# neuztech-4.net
KiCad netlist of a schematic drawn in EAGLE
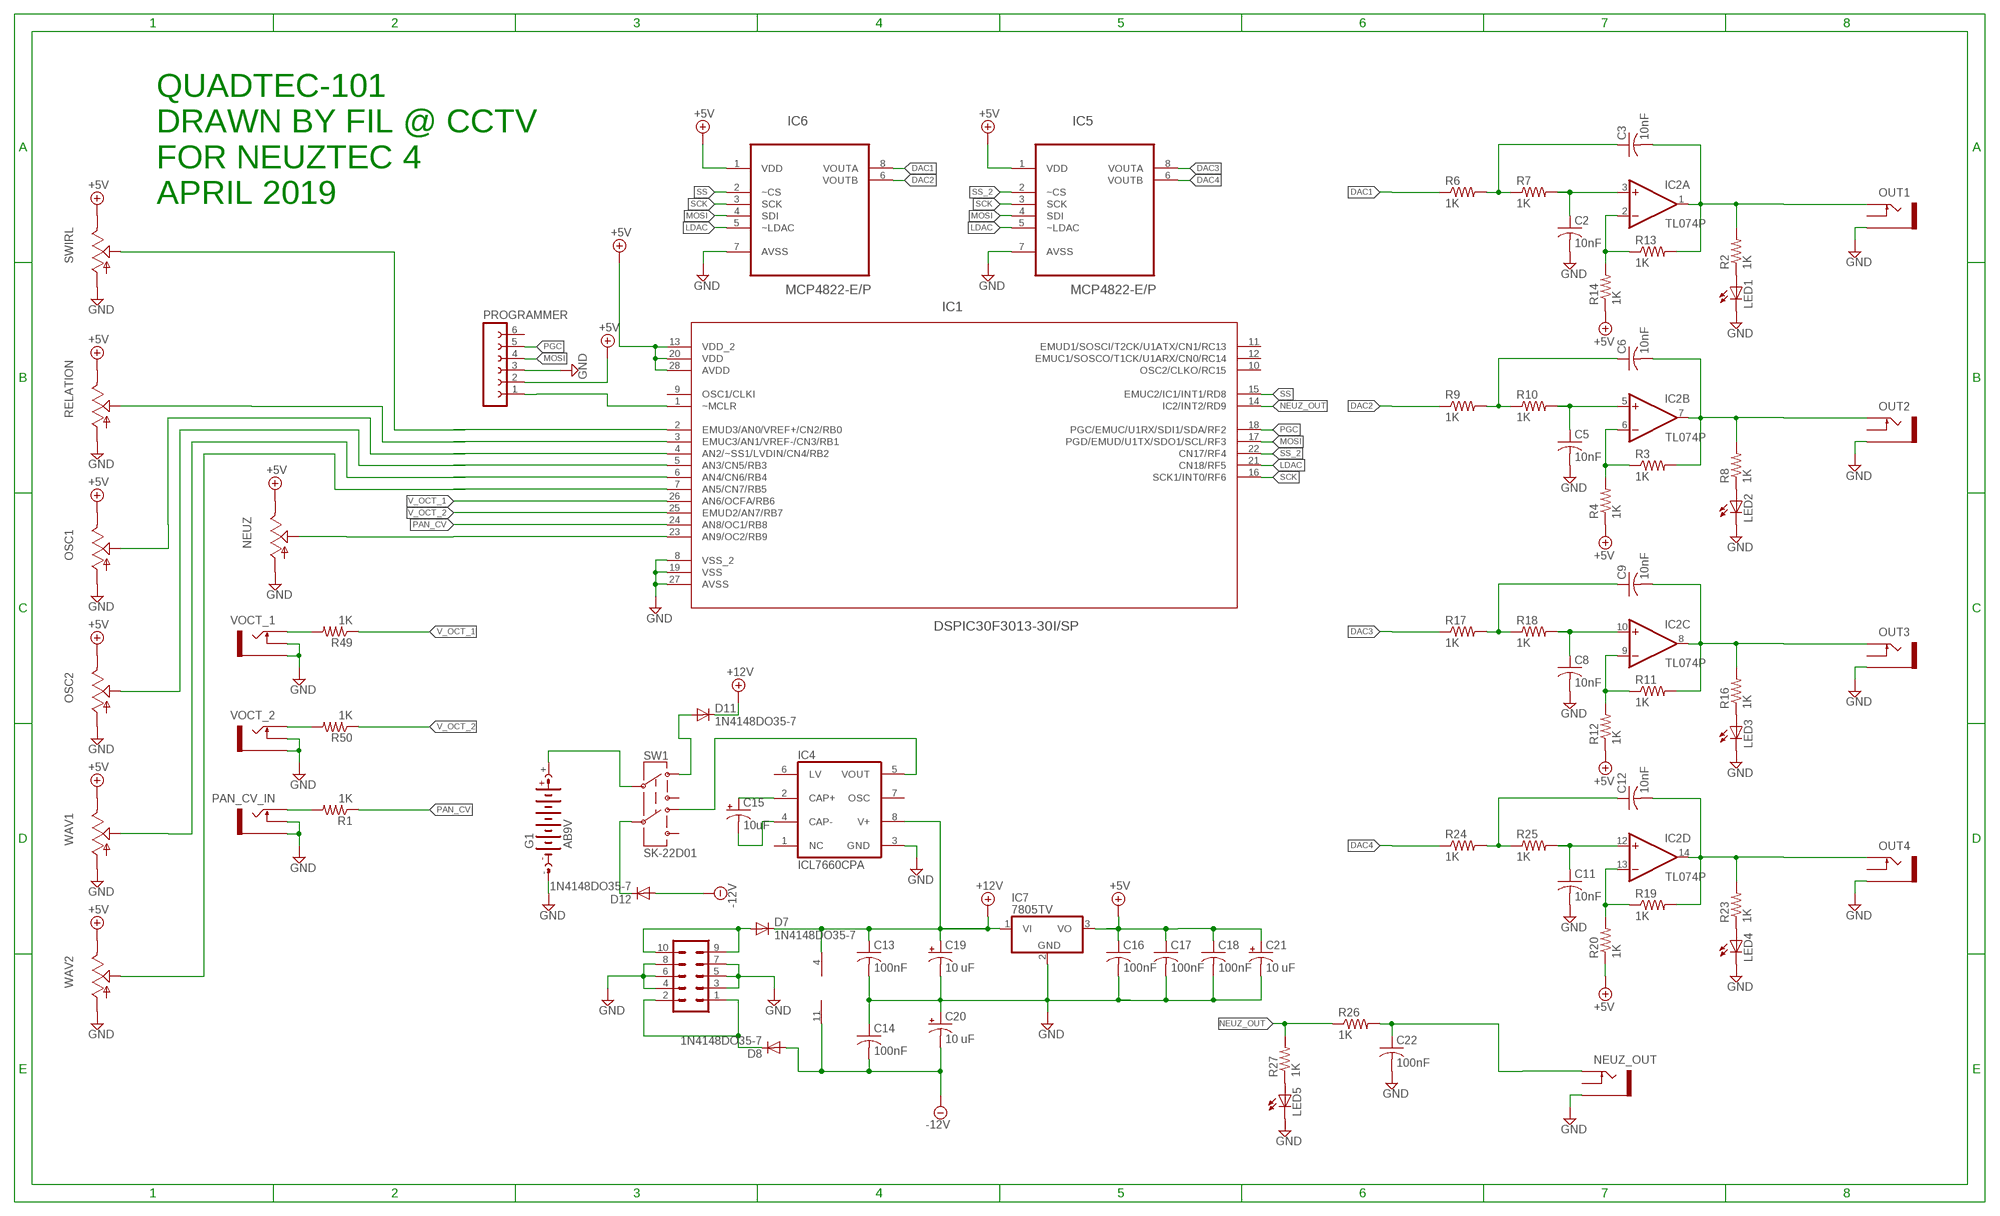
[diagram p0: schematic, sheet 1]

(export (version "E")
  (design (tool "Eeschema 10.0.6"))
  (components
    (comp (ref "C2")
      (value "10nF")
      (footprint "eagle-import:C050-035X075")
      (libsource (lib "eagle-import") (part "C-US050-035X075"))
    )
    (comp (ref "C3")
      (value "10nF")
      (footprint "eagle-import:C050-035X075")
      (libsource (lib "eagle-import") (part "C-US050-035X075"))
    )
    (comp (ref "C5")
      (value "10nF")
      (footprint "eagle-import:C050-035X075")
      (libsource (lib "eagle-import") (part "C-US050-035X075"))
    )
    (comp (ref "C6")
      (value "10nF")
      (footprint "eagle-import:C050-035X075")
      (libsource (lib "eagle-import") (part "C-US050-035X075"))
    )
    (comp (ref "C8")
      (value "10nF")
      (footprint "eagle-import:C050-035X075")
      (libsource (lib "eagle-import") (part "C-US050-035X075"))
    )
    (comp (ref "C9")
      (value "10nF")
      (footprint "eagle-import:C050-035X075")
      (libsource (lib "eagle-import") (part "C-US050-035X075"))
    )
    (comp (ref "C11")
      (value "10nF")
      (footprint "eagle-import:C050-035X075")
      (libsource (lib "eagle-import") (part "C-US050-035X075"))
    )
    (comp (ref "C12")
      (value "10nF")
      (footprint "eagle-import:C050-035X075")
      (libsource (lib "eagle-import") (part "C-US050-035X075"))
    )
    (comp (ref "C13")
      (value "100nF")
      (footprint "eagle-import:C050-024X044")
      (libsource (lib "eagle-import") (part "C-US050-024X044"))
    )
    (comp (ref "C14")
      (value "100nF")
      (footprint "eagle-import:C050-024X044")
      (libsource (lib "eagle-import") (part "C-US050-024X044"))
    )
    (comp (ref "C15")
      (value "10uF")
      (footprint "eagle-import:E2-4")
      (libsource (lib "eagle-import") (part "CPOL-USE2-4"))
    )
    (comp (ref "C16")
      (value "100nF")
      (footprint "eagle-import:C050-024X044")
      (libsource (lib "eagle-import") (part "C-US050-024X044"))
    )
    (comp (ref "C17")
      (value "100nF")
      (footprint "eagle-import:C050-024X044")
      (libsource (lib "eagle-import") (part "C-US050-024X044"))
    )
    (comp (ref "C18")
      (value "100nF")
      (footprint "eagle-import:C050-024X044")
      (libsource (lib "eagle-import") (part "C-US050-024X044"))
    )
    (comp (ref "C19")
      (value "10 uF")
      (footprint "eagle-import:E2-4")
      (libsource (lib "eagle-import") (part "CPOL-USE2-4"))
    )
    (comp (ref "C20")
      (value "10 uF")
      (footprint "eagle-import:E2-4")
      (libsource (lib "eagle-import") (part "CPOL-USE2-4"))
    )
    (comp (ref "C21")
      (value "10 uF")
      (footprint "eagle-import:E2-4")
      (libsource (lib "eagle-import") (part "CPOL-USE2-4"))
    )
    (comp (ref "C22")
      (value "100nF")
      (footprint "eagle-import:C050-024X044")
      (libsource (lib "eagle-import") (part "C-US050-024X044"))
    )
    (comp (ref "D7")
      (value "1N4148DO35-7")
      (footprint "eagle-import:DO35-7")
      (libsource (lib "eagle-import") (part "1N4148DO35-7"))
    )
    (comp (ref "D8")
      (value "1N4148DO35-7")
      (footprint "eagle-import:DO35-7")
      (libsource (lib "eagle-import") (part "1N4148DO35-7"))
    )
    (comp (ref "D11")
      (value "1N4148DO35-7")
      (footprint "eagle-import:DO35-7")
      (libsource (lib "eagle-import") (part "1N4148DO35-7"))
    )
    (comp (ref "D12")
      (value "1N4148DO35-7")
      (footprint "eagle-import:DO35-7")
      (libsource (lib "eagle-import") (part "1N4148DO35-7"))
    )
    (comp (ref "G1")
      (value "AB9V")
      (footprint "eagle-import:AB9V")
      (libsource (lib "eagle-import") (part "AB9V"))
    )
    (comp (ref "IC1")
      (value "DSPIC30F3013-30I/SP")
      (footprint "eagle-import:DIP254P762X508-28")
      (fields (field (name "MF") "Microchip"))
      (libsource (lib "eagle-import") (part "DSPIC30F3013-30I/SP"))
    )
    (comp (ref "IC2")
      (value "TL074P")
      (footprint "eagle-import:DIL14")
      (libsource (lib "eagle-import") (part "TL074P"))
    )
    (comp (ref "IC4")
      (value "ICL7660CPA")
      (footprint "eagle-import:DIL08")
      (fields (field (name "MF") "INTERSIL"))
      (libsource (lib "eagle-import") (part "ICL7660CPA"))
    )
    (comp (ref "IC5")
      (value "MCP4822-E/P")
      (footprint "eagle-import:DIP254P762X432-8")
      (fields (field (name "MF") "Microchip"))
      (libsource (lib "eagle-import") (part "MCP4822-E/P"))
    )
    (comp (ref "IC6")
      (value "MCP4822-E/P")
      (footprint "eagle-import:DIP254P762X432-8")
      (fields (field (name "MF") "Microchip"))
      (libsource (lib "eagle-import") (part "MCP4822-E/P"))
    )
    (comp (ref "IC7")
      (value "7805TV")
      (footprint "eagle-import:TO220V")
      (libsource (lib "eagle-import") (part "78TV05"))
    )
    (comp (ref "LED1")
      (value "LED3MM")
      (footprint "eagle-import:LED3MM")
      (libsource (lib "eagle-import") (part "LED3MM"))
    )
    (comp (ref "LED2")
      (value "LED3MM")
      (footprint "eagle-import:LED3MM")
      (libsource (lib "eagle-import") (part "LED3MM"))
    )
    (comp (ref "LED3")
      (value "LED3MM")
      (footprint "eagle-import:LED3MM")
      (libsource (lib "eagle-import") (part "LED3MM"))
    )
    (comp (ref "LED4")
      (value "LED3MM")
      (footprint "eagle-import:LED3MM")
      (libsource (lib "eagle-import") (part "LED3MM"))
    )
    (comp (ref "LED5")
      (value "LED3MM")
      (footprint "eagle-import:LED3MM")
      (libsource (lib "eagle-import") (part "LED3MM"))
    )
    (comp (ref "NEUZ")
      (value "9MM_SNAP-IN_POT_")
      (footprint "eagle-import:9MM_SNAP-IN_POT")
      (libsource (lib "eagle-import") (part "9MM_SNAP-IN_POT_"))
    )
    (comp (ref "NEUZ_OUT")
      (value "THONKICONNNEW")
      (footprint "eagle-import:WQP-PJ301M-12_JACK")
      (libsource (lib "eagle-import") (part "THONKICONNNEW"))
    )
    (comp (ref "OSC1")
      (value "9MM_SNAP-IN_POT_")
      (footprint "eagle-import:9MM_SNAP-IN_POT")
      (libsource (lib "eagle-import") (part "9MM_SNAP-IN_POT_"))
    )
    (comp (ref "OSC2")
      (value "9MM_SNAP-IN_POT_")
      (footprint "eagle-import:9MM_SNAP-IN_POT")
      (libsource (lib "eagle-import") (part "9MM_SNAP-IN_POT_"))
    )
    (comp (ref "OUT1")
      (value "THONKICONNNEW")
      (footprint "eagle-import:WQP-PJ301M-12_JACK")
      (libsource (lib "eagle-import") (part "THONKICONNNEW"))
    )
    (comp (ref "OUT2")
      (value "THONKICONNNEW")
      (footprint "eagle-import:WQP-PJ301M-12_JACK")
      (libsource (lib "eagle-import") (part "THONKICONNNEW"))
    )
    (comp (ref "OUT3")
      (value "THONKICONNNEW")
      (footprint "eagle-import:WQP-PJ301M-12_JACK")
      (libsource (lib "eagle-import") (part "THONKICONNNEW"))
    )
    (comp (ref "OUT4")
      (value "THONKICONNNEW")
      (footprint "eagle-import:WQP-PJ301M-12_JACK")
      (libsource (lib "eagle-import") (part "THONKICONNNEW"))
    )
    (comp (ref "PAN_CV_IN")
      (value "THONKICONNNEW")
      (footprint "eagle-import:WQP-PJ301M-12_JACK")
      (libsource (lib "eagle-import") (part "THONKICONNNEW"))
    )
    (comp (ref "PROGRAMMER")
      (value "FE06-1")
      (footprint "eagle-import:FE06")
      (libsource (lib "eagle-import") (part "FE06-1"))
    )
    (comp (ref "R1")
      (value "1K")
      (footprint "eagle-import:0207_10")
      (libsource (lib "eagle-import") (part "R-US_0207/10"))
    )
    (comp (ref "R2")
      (value "1K")
      (footprint "eagle-import:0207_10")
      (libsource (lib "eagle-import") (part "R-US_0207/10"))
    )
    (comp (ref "R3")
      (value "1K")
      (footprint "eagle-import:0207_10")
      (libsource (lib "eagle-import") (part "R-US_0207/10"))
    )
    (comp (ref "R4")
      (value "1K")
      (footprint "eagle-import:0207_10")
      (libsource (lib "eagle-import") (part "R-US_0207/10"))
    )
    (comp (ref "R6")
      (value "1K")
      (footprint "eagle-import:0207_10")
      (libsource (lib "eagle-import") (part "R-US_0207/10"))
    )
    (comp (ref "R7")
      (value "1K")
      (footprint "eagle-import:0207_10")
      (libsource (lib "eagle-import") (part "R-US_0207/10"))
    )
    (comp (ref "R8")
      (value "1K")
      (footprint "eagle-import:0207_10")
      (libsource (lib "eagle-import") (part "R-US_0207/10"))
    )
    (comp (ref "R9")
      (value "1K")
      (footprint "eagle-import:0207_10")
      (libsource (lib "eagle-import") (part "R-US_0207/10"))
    )
    (comp (ref "R10")
      (value "1K")
      (footprint "eagle-import:0207_10")
      (libsource (lib "eagle-import") (part "R-US_0207/10"))
    )
    (comp (ref "R11")
      (value "1K")
      (footprint "eagle-import:0207_10")
      (libsource (lib "eagle-import") (part "R-US_0207/10"))
    )
    (comp (ref "R12")
      (value "1K")
      (footprint "eagle-import:0207_10")
      (libsource (lib "eagle-import") (part "R-US_0207/10"))
    )
    (comp (ref "R13")
      (value "1K")
      (footprint "eagle-import:0207_10")
      (libsource (lib "eagle-import") (part "R-US_0207/10"))
    )
    (comp (ref "R14")
      (value "1K")
      (footprint "eagle-import:0207_10")
      (libsource (lib "eagle-import") (part "R-US_0207/10"))
    )
    (comp (ref "R16")
      (value "1K")
      (footprint "eagle-import:0207_10")
      (libsource (lib "eagle-import") (part "R-US_0207/10"))
    )
    (comp (ref "R17")
      (value "1K")
      (footprint "eagle-import:0207_10")
      (libsource (lib "eagle-import") (part "R-US_0207/10"))
    )
    (comp (ref "R18")
      (value "1K")
      (footprint "eagle-import:0207_10")
      (libsource (lib "eagle-import") (part "R-US_0207/10"))
    )
    (comp (ref "R19")
      (value "1K")
      (footprint "eagle-import:0207_10")
      (libsource (lib "eagle-import") (part "R-US_0207/10"))
    )
    (comp (ref "R20")
      (value "1K")
      (footprint "eagle-import:0207_10")
      (libsource (lib "eagle-import") (part "R-US_0207/10"))
    )
    (comp (ref "R23")
      (value "1K")
      (footprint "eagle-import:0207_10")
      (libsource (lib "eagle-import") (part "R-US_0207/10"))
    )
    (comp (ref "R24")
      (value "1K")
      (footprint "eagle-import:0207_10")
      (libsource (lib "eagle-import") (part "R-US_0207/10"))
    )
    (comp (ref "R25")
      (value "1K")
      (footprint "eagle-import:0207_10")
      (libsource (lib "eagle-import") (part "R-US_0207/10"))
    )
    (comp (ref "R26")
      (value "1K")
      (footprint "eagle-import:0207_10")
      (libsource (lib "eagle-import") (part "R-US_0207/10"))
    )
    (comp (ref "R27")
      (value "1K")
      (footprint "eagle-import:0207_10")
      (libsource (lib "eagle-import") (part "R-US_0207/10"))
    )
    (comp (ref "R49")
      (value "1K")
      (footprint "eagle-import:0207_10")
      (libsource (lib "eagle-import") (part "R-US_0207/10"))
    )
    (comp (ref "R50")
      (value "1K")
      (footprint "eagle-import:0207_10")
      (libsource (lib "eagle-import") (part "R-US_0207/10"))
    )
    (comp (ref "RELATION")
      (value "9MM_SNAP-IN_POT_")
      (footprint "eagle-import:9MM_SNAP-IN_POT")
      (libsource (lib "eagle-import") (part "9MM_SNAP-IN_POT_"))
    )
    (comp (ref "SV2")
      (value "EURO_POWER_HEADERFAT_PADS")
      (footprint "eagle-import:EURO_PWR_HEADER_FAT")
      (libsource (lib "eagle-import") (part "EURO_POWER_HEADERFAT_PADS"))
    )
    (comp (ref "SW1")
      (value "SK-22D01")
      (footprint "eagle-import:SK-22D01-MG")
      (libsource (lib "eagle-import") (part "SK-22D01"))
    )
    (comp (ref "SWIRL")
      (value "9MM_SNAP-IN_POT_")
      (footprint "eagle-import:9MM_SNAP-IN_POT")
      (libsource (lib "eagle-import") (part "9MM_SNAP-IN_POT_"))
    )
    (comp (ref "VOCT_1")
      (value "THONKICONNNEW")
      (footprint "eagle-import:WQP-PJ301M-12_JACK")
      (libsource (lib "eagle-import") (part "THONKICONNNEW"))
    )
    (comp (ref "VOCT_2")
      (value "THONKICONNNEW")
      (footprint "eagle-import:WQP-PJ301M-12_JACK")
      (libsource (lib "eagle-import") (part "THONKICONNNEW"))
    )
    (comp (ref "WAV1")
      (value "9MM_SNAP-IN_POT_")
      (footprint "eagle-import:9MM_SNAP-IN_POT")
      (libsource (lib "eagle-import") (part "9MM_SNAP-IN_POT_"))
    )
    (comp (ref "WAV2")
      (value "9MM_SNAP-IN_POT_")
      (footprint "eagle-import:9MM_SNAP-IN_POT")
      (libsource (lib "eagle-import") (part "9MM_SNAP-IN_POT_"))
    )
  )
  (nets
    (net (code "1") (name "+5V") (class "Default")
      (node (ref "C16") (pin "1") (pinfunction "1_1") (pintype "passive"))
      (node (ref "C17") (pin "1") (pinfunction "1_1") (pintype "passive"))
      (node (ref "C18") (pin "1") (pinfunction "1_1") (pintype "passive"))
      (node (ref "C21") (pin "+") (pinfunction "+_+") (pintype "passive"))
      (node (ref "IC1") (pin "13") (pinfunction "VDD_2_13") (pintype "power_in"))
      (node (ref "IC1") (pin "20") (pinfunction "VDD_20") (pintype "power_in"))
      (node (ref "IC1") (pin "28") (pinfunction "AVDD_28") (pintype "passive"))
      (node (ref "IC5") (pin "1") (pinfunction "VDD_1") (pintype "power_in"))
      (node (ref "IC6") (pin "1") (pinfunction "VDD_1") (pintype "power_in"))
      (node (ref "IC7") (pin "3") (pinfunction "VO_3") (pintype "passive"))
      (node (ref "NEUZ") (pin "3") (pinfunction "E_3") (pintype "passive"))
      (node (ref "OSC1") (pin "3") (pinfunction "E_3") (pintype "passive"))
      (node (ref "OSC2") (pin "3") (pinfunction "E_3") (pintype "passive"))
      (node (ref "PROGRAMMER") (pin "2") (pinfunction "2_2") (pintype "passive"))
      (node (ref "R12") (pin "1") (pinfunction "1_1") (pintype "passive"))
      (node (ref "R14") (pin "1") (pinfunction "1_1") (pintype "passive"))
      (node (ref "R20") (pin "1") (pinfunction "1_1") (pintype "passive"))
      (node (ref "R4") (pin "1") (pinfunction "1_1") (pintype "passive"))
      (node (ref "RELATION") (pin "3") (pinfunction "E_3") (pintype "passive"))
      (node (ref "SWIRL") (pin "3") (pinfunction "E_3") (pintype "passive"))
      (node (ref "WAV1") (pin "3") (pinfunction "E_3") (pintype "passive"))
      (node (ref "WAV2") (pin "3") (pinfunction "E_3") (pintype "passive"))
    )
    (net (code "2") (name "+12V") (class "Default")
      (node (ref "C13") (pin "1") (pinfunction "1_1") (pintype "passive"))
      (node (ref "C19") (pin "+") (pinfunction "+_+") (pintype "passive"))
      (node (ref "D11") (pin "C") (pinfunction "C_C") (pintype "passive"))
      (node (ref "D7") (pin "C") (pinfunction "C_C") (pintype "passive"))
      (node (ref "IC2") (pin "4") (pinfunction "V+_4") (pintype "power_in"))
      (node (ref "IC4") (pin "8") (pinfunction "V+_8") (pintype "power_in"))
      (node (ref "IC7") (pin "1") (pinfunction "VI_1") (pintype "input"))
    )
    (net (code "3") (name "-12V") (class "Default")
      (node (ref "C14") (pin "2") (pinfunction "2_2") (pintype "passive"))
      (node (ref "C20") (pin "-") (pinfunction "-_-") (pintype "passive"))
      (node (ref "D12") (pin "A") (pinfunction "A_A") (pintype "passive"))
      (node (ref "D8") (pin "A") (pinfunction "A_A") (pintype "passive"))
      (node (ref "IC2") (pin "11") (pinfunction "V-_11") (pintype "power_in"))
    )
    (net (code "4") (name "DAC1") (class "Default")
      (node (ref "IC6") (pin "8") (pinfunction "VOUTA_8") (pintype "output"))
      (node (ref "R6") (pin "1") (pinfunction "1_1") (pintype "passive"))
    )
    (net (code "5") (name "DAC2") (class "Default")
      (node (ref "IC6") (pin "6") (pinfunction "VOUTB_6") (pintype "output"))
      (node (ref "R9") (pin "1") (pinfunction "1_1") (pintype "passive"))
    )
    (net (code "6") (name "DAC3") (class "Default")
      (node (ref "IC5") (pin "8") (pinfunction "VOUTA_8") (pintype "output"))
      (node (ref "R17") (pin "1") (pinfunction "1_1") (pintype "passive"))
    )
    (net (code "7") (name "DAC4") (class "Default")
      (node (ref "IC5") (pin "6") (pinfunction "VOUTB_6") (pintype "output"))
      (node (ref "R24") (pin "1") (pinfunction "1_1") (pintype "passive"))
    )
    (net (code "8") (name "GND") (class "Default")
      (node (ref "C11") (pin "2") (pinfunction "2_2") (pintype "passive"))
      (node (ref "C13") (pin "2") (pinfunction "2_2") (pintype "passive"))
      (node (ref "C14") (pin "1") (pinfunction "1_1") (pintype "passive"))
      (node (ref "C16") (pin "2") (pinfunction "2_2") (pintype "passive"))
      (node (ref "C17") (pin "2") (pinfunction "2_2") (pintype "passive"))
      (node (ref "C18") (pin "2") (pinfunction "2_2") (pintype "passive"))
      (node (ref "C19") (pin "-") (pinfunction "-_-") (pintype "passive"))
      (node (ref "C2") (pin "2") (pinfunction "2_2") (pintype "passive"))
      (node (ref "C20") (pin "+") (pinfunction "+_+") (pintype "passive"))
      (node (ref "C21") (pin "-") (pinfunction "-_-") (pintype "passive"))
      (node (ref "C22") (pin "2") (pinfunction "2_2") (pintype "passive"))
      (node (ref "C5") (pin "2") (pinfunction "2_2") (pintype "passive"))
      (node (ref "C8") (pin "2") (pinfunction "2_2") (pintype "passive"))
      (node (ref "G1") (pin "-") (pinfunction "-_-") (pintype "passive"))
      (node (ref "IC1") (pin "19") (pinfunction "VSS_19") (pintype "power_in"))
      (node (ref "IC1") (pin "27") (pinfunction "AVSS_27") (pintype "passive"))
      (node (ref "IC1") (pin "8") (pinfunction "VSS_2_8") (pintype "power_in"))
      (node (ref "IC4") (pin "3") (pinfunction "GND_3") (pintype "power_in"))
      (node (ref "IC5") (pin "7") (pinfunction "AVSS_7") (pintype "passive"))
      (node (ref "IC6") (pin "7") (pinfunction "AVSS_7") (pintype "passive"))
      (node (ref "IC7") (pin "2") (pinfunction "GND_2") (pintype "passive"))
      (node (ref "LED1") (pin "K") (pinfunction "C_K") (pintype "passive"))
      (node (ref "LED2") (pin "K") (pinfunction "C_K") (pintype "passive"))
      (node (ref "LED3") (pin "K") (pinfunction "C_K") (pintype "passive"))
      (node (ref "LED4") (pin "K") (pinfunction "C_K") (pintype "passive"))
      (node (ref "LED5") (pin "K") (pinfunction "C_K") (pintype "passive"))
      (node (ref "NEUZ") (pin "1") (pinfunction "A_1") (pintype "passive"))
      (node (ref "NEUZ_OUT") (pin "P$3_SLEEVE") (pinfunction "SLEEVE_P$3_SLEEVE") (pintype "passive"))
      (node (ref "OSC1") (pin "1") (pinfunction "A_1") (pintype "passive"))
      (node (ref "OSC2") (pin "1") (pinfunction "A_1") (pintype "passive"))
      (node (ref "OUT1") (pin "P$3_SLEEVE") (pinfunction "SLEEVE_P$3_SLEEVE") (pintype "passive"))
      (node (ref "OUT2") (pin "P$3_SLEEVE") (pinfunction "SLEEVE_P$3_SLEEVE") (pintype "passive"))
      (node (ref "OUT3") (pin "P$3_SLEEVE") (pinfunction "SLEEVE_P$3_SLEEVE") (pintype "passive"))
      (node (ref "OUT4") (pin "P$3_SLEEVE") (pinfunction "SLEEVE_P$3_SLEEVE") (pintype "passive"))
      (node (ref "PAN_CV_IN") (pin "P$2_SWITCH") (pinfunction "SWITCH_P$2_SWITCH") (pintype "passive"))
      (node (ref "PAN_CV_IN") (pin "P$3_SLEEVE") (pinfunction "SLEEVE_P$3_SLEEVE") (pintype "passive"))
      (node (ref "PROGRAMMER") (pin "3") (pinfunction "3_3") (pintype "passive"))
      (node (ref "RELATION") (pin "1") (pinfunction "A_1") (pintype "passive"))
      (node (ref "SV2") (pin "3") (pinfunction "3_3") (pintype "passive"))
      (node (ref "SV2") (pin "4") (pinfunction "4_4") (pintype "passive"))
      (node (ref "SV2") (pin "5") (pinfunction "5_5") (pintype "passive"))
      (node (ref "SV2") (pin "6") (pinfunction "6_6") (pintype "passive"))
      (node (ref "SV2") (pin "7") (pinfunction "7_7") (pintype "passive"))
      (node (ref "SV2") (pin "8") (pinfunction "8_8") (pintype "passive"))
      (node (ref "SWIRL") (pin "1") (pinfunction "A_1") (pintype "passive"))
      (node (ref "VOCT_1") (pin "P$2_SWITCH") (pinfunction "SWITCH_P$2_SWITCH") (pintype "passive"))
      (node (ref "VOCT_1") (pin "P$3_SLEEVE") (pinfunction "SLEEVE_P$3_SLEEVE") (pintype "passive"))
      (node (ref "VOCT_2") (pin "P$2_SWITCH") (pinfunction "SWITCH_P$2_SWITCH") (pintype "passive"))
      (node (ref "VOCT_2") (pin "P$3_SLEEVE") (pinfunction "SLEEVE_P$3_SLEEVE") (pintype "passive"))
      (node (ref "WAV1") (pin "1") (pinfunction "A_1") (pintype "passive"))
      (node (ref "WAV2") (pin "1") (pinfunction "A_1") (pintype "passive"))
    )
    (net (code "9") (name "LDAC") (class "Default")
      (node (ref "IC1") (pin "21") (pinfunction "CN18/RF5_21") (pintype "bidirectional"))
      (node (ref "IC5") (pin "5") (pinfunction "~{LDAC}_5") (pintype "input"))
      (node (ref "IC6") (pin "5") (pinfunction "~{LDAC}_5") (pintype "input"))
    )
    (net (code "10") (name "MOSI") (class "Default")
      (node (ref "IC1") (pin "17") (pinfunction "PGD/EMUD/U1TX/SDO1/SCL/RF3_17") (pintype "bidirectional"))
      (node (ref "IC5") (pin "4") (pinfunction "SDI_4") (pintype "input"))
      (node (ref "IC6") (pin "4") (pinfunction "SDI_4") (pintype "input"))
      (node (ref "PROGRAMMER") (pin "4") (pinfunction "4_4") (pintype "passive"))
    )
    (net (code "11") (name "NEUZ_OUT") (class "Default")
      (node (ref "IC1") (pin "14") (pinfunction "IC2/INT2/RD9_14") (pintype "bidirectional"))
      (node (ref "R26") (pin "1") (pinfunction "1_1") (pintype "passive"))
      (node (ref "R27") (pin "2") (pinfunction "2_2") (pintype "passive"))
    )
    (net (code "12") (name "Net-(C3-Pad1)") (class "Default")
      (node (ref "C3") (pin "1") (pinfunction "1_1") (pintype "passive"))
      (node (ref "R6") (pin "2") (pinfunction "2_2") (pintype "passive"))
      (node (ref "R7") (pin "1") (pinfunction "1_1") (pintype "passive"))
    )
    (net (code "13") (name "Net-(C6-Pad1)") (class "Default")
      (node (ref "C6") (pin "1") (pinfunction "1_1") (pintype "passive"))
      (node (ref "R10") (pin "1") (pinfunction "1_1") (pintype "passive"))
      (node (ref "R9") (pin "2") (pinfunction "2_2") (pintype "passive"))
    )
    (net (code "14") (name "Net-(C9-Pad1)") (class "Default")
      (node (ref "C9") (pin "1") (pinfunction "1_1") (pintype "passive"))
      (node (ref "R17") (pin "2") (pinfunction "2_2") (pintype "passive"))
      (node (ref "R18") (pin "1") (pinfunction "1_1") (pintype "passive"))
    )
    (net (code "15") (name "Net-(C12-Pad1)") (class "Default")
      (node (ref "C12") (pin "1") (pinfunction "1_1") (pintype "passive"))
      (node (ref "R24") (pin "2") (pinfunction "2_2") (pintype "passive"))
      (node (ref "R25") (pin "1") (pinfunction "1_1") (pintype "passive"))
    )
    (net (code "16") (name "Net-(D7-PadA)") (class "Default")
      (node (ref "D7") (pin "A") (pinfunction "A_A") (pintype "passive"))
      (node (ref "SV2") (pin "10") (pinfunction "10_10") (pintype "passive"))
      (node (ref "SV2") (pin "9") (pinfunction "9_9") (pintype "passive"))
    )
    (net (code "17") (name "Net-(D8-PadC)") (class "Default")
      (node (ref "D8") (pin "C") (pinfunction "C_C") (pintype "passive"))
      (node (ref "SV2") (pin "1") (pinfunction "1_1") (pintype "passive"))
      (node (ref "SV2") (pin "2") (pinfunction "2_2") (pintype "passive"))
    )
    (net (code "18") (name "Net-(D12-PadC)") (class "Default")
      (node (ref "D12") (pin "C") (pinfunction "C_C") (pintype "passive"))
      (node (ref "SW1") (pin "C2") (pinfunction "C2_C2") (pintype "bidirectional"))
    )
    (net (code "19") (name "Net-(IC1-AN2{slash}~{SS1{slash}LVDIN{slash}CN4{slash}RB2})") (class "Default")
      (node (ref "IC1") (pin "4") (pinfunction "AN2/~{SS1/LVDIN/CN4/RB2}_4") (pintype "bidirectional"))
      (node (ref "OSC1") (pin "2") (pinfunction "S_2") (pintype "passive"))
    )
    (net (code "20") (name "Net-(IC1-AN3{slash}CN5{slash}RB3)") (class "Default")
      (node (ref "IC1") (pin "5") (pinfunction "AN3/CN5/RB3_5") (pintype "bidirectional"))
      (node (ref "OSC2") (pin "2") (pinfunction "S_2") (pintype "passive"))
    )
    (net (code "21") (name "Net-(IC1-AN4{slash}CN6{slash}RB4)") (class "Default")
      (node (ref "IC1") (pin "6") (pinfunction "AN4/CN6/RB4_6") (pintype "bidirectional"))
      (node (ref "WAV1") (pin "2") (pinfunction "S_2") (pintype "passive"))
    )
    (net (code "22") (name "Net-(IC1-AN5{slash}CN7{slash}RB5)") (class "Default")
      (node (ref "IC1") (pin "7") (pinfunction "AN5/CN7/RB5_7") (pintype "bidirectional"))
      (node (ref "WAV2") (pin "2") (pinfunction "S_2") (pintype "passive"))
    )
    (net (code "23") (name "Net-(IC1-AN9{slash}OC2{slash}RB9)") (class "Default")
      (node (ref "IC1") (pin "23") (pinfunction "AN9/OC2/RB9_23") (pintype "bidirectional"))
      (node (ref "NEUZ") (pin "2") (pinfunction "S_2") (pintype "passive"))
    )
    (net (code "24") (name "Net-(IC1-EMUC3{slash}AN1{slash}VREF-{slash}CN3{slash}RB1)") (class "Default")
      (node (ref "IC1") (pin "3") (pinfunction "EMUC3/AN1/VREF-/CN3/RB1_3") (pintype "bidirectional"))
      (node (ref "RELATION") (pin "2") (pinfunction "S_2") (pintype "passive"))
    )
    (net (code "25") (name "Net-(IC1-EMUD3{slash}AN0{slash}VREF+{slash}CN2{slash}RB0)") (class "Default")
      (node (ref "IC1") (pin "2") (pinfunction "EMUD3/AN0/VREF+/CN2/RB0_2") (pintype "bidirectional"))
      (node (ref "SWIRL") (pin "2") (pinfunction "S_2") (pintype "passive"))
    )
    (net (code "26") (name "Net-(IC1-~{MCLR})") (class "Default")
      (node (ref "IC1") (pin "1") (pinfunction "~{MCLR}_1") (pintype "input"))
      (node (ref "PROGRAMMER") (pin "1") (pinfunction "1_1") (pintype "passive"))
    )
    (net (code "27") (name "Net-(IC2A-+IN)") (class "Default")
      (node (ref "C2") (pin "1") (pinfunction "1_1") (pintype "passive"))
      (node (ref "IC2") (pin "3") (pinfunction "+IN_3") (pintype "input"))
      (node (ref "R7") (pin "2") (pinfunction "2_2") (pintype "passive"))
    )
    (net (code "28") (name "Net-(IC2A--IN)") (class "Default")
      (node (ref "IC2") (pin "2") (pinfunction "-IN_2") (pintype "input"))
      (node (ref "R13") (pin "1") (pinfunction "1_1") (pintype "passive"))
      (node (ref "R14") (pin "2") (pinfunction "2_2") (pintype "passive"))
    )
    (net (code "29") (name "Net-(IC2A-OUT)") (class "Default")
      (node (ref "C3") (pin "2") (pinfunction "2_2") (pintype "passive"))
      (node (ref "IC2") (pin "1") (pinfunction "OUT_1") (pintype "output"))
      (node (ref "OUT1") (pin "P$1_TIP") (pinfunction "TIP_P$1_TIP") (pintype "passive"))
      (node (ref "R13") (pin "2") (pinfunction "2_2") (pintype "passive"))
      (node (ref "R2") (pin "2") (pinfunction "2_2") (pintype "passive"))
    )
    (net (code "30") (name "Net-(IC2B-+IN)") (class "Default")
      (node (ref "C5") (pin "1") (pinfunction "1_1") (pintype "passive"))
      (node (ref "IC2") (pin "5") (pinfunction "+IN_5") (pintype "input"))
      (node (ref "R10") (pin "2") (pinfunction "2_2") (pintype "passive"))
    )
    (net (code "31") (name "Net-(IC2B--IN)") (class "Default")
      (node (ref "IC2") (pin "6") (pinfunction "-IN_6") (pintype "input"))
      (node (ref "R3") (pin "1") (pinfunction "1_1") (pintype "passive"))
      (node (ref "R4") (pin "2") (pinfunction "2_2") (pintype "passive"))
    )
    (net (code "32") (name "Net-(IC2B-OUT)") (class "Default")
      (node (ref "C6") (pin "2") (pinfunction "2_2") (pintype "passive"))
      (node (ref "IC2") (pin "7") (pinfunction "OUT_7") (pintype "output"))
      (node (ref "OUT2") (pin "P$1_TIP") (pinfunction "TIP_P$1_TIP") (pintype "passive"))
      (node (ref "R3") (pin "2") (pinfunction "2_2") (pintype "passive"))
      (node (ref "R8") (pin "2") (pinfunction "2_2") (pintype "passive"))
    )
    (net (code "33") (name "Net-(IC2C-+IN)") (class "Default")
      (node (ref "C8") (pin "1") (pinfunction "1_1") (pintype "passive"))
      (node (ref "IC2") (pin "10") (pinfunction "+IN_10") (pintype "input"))
      (node (ref "R18") (pin "2") (pinfunction "2_2") (pintype "passive"))
    )
    (net (code "34") (name "Net-(IC2C--IN)") (class "Default")
      (node (ref "IC2") (pin "9") (pinfunction "-IN_9") (pintype "input"))
      (node (ref "R11") (pin "1") (pinfunction "1_1") (pintype "passive"))
      (node (ref "R12") (pin "2") (pinfunction "2_2") (pintype "passive"))
    )
    (net (code "35") (name "Net-(IC2C-OUT)") (class "Default")
      (node (ref "C9") (pin "2") (pinfunction "2_2") (pintype "passive"))
      (node (ref "IC2") (pin "8") (pinfunction "OUT_8") (pintype "output"))
      (node (ref "OUT3") (pin "P$1_TIP") (pinfunction "TIP_P$1_TIP") (pintype "passive"))
      (node (ref "R11") (pin "2") (pinfunction "2_2") (pintype "passive"))
      (node (ref "R16") (pin "2") (pinfunction "2_2") (pintype "passive"))
    )
    (net (code "36") (name "Net-(IC2D-+IN)") (class "Default")
      (node (ref "C11") (pin "1") (pinfunction "1_1") (pintype "passive"))
      (node (ref "IC2") (pin "12") (pinfunction "+IN_12") (pintype "input"))
      (node (ref "R25") (pin "2") (pinfunction "2_2") (pintype "passive"))
    )
    (net (code "37") (name "Net-(IC2D--IN)") (class "Default")
      (node (ref "IC2") (pin "13") (pinfunction "-IN_13") (pintype "input"))
      (node (ref "R19") (pin "1") (pinfunction "1_1") (pintype "passive"))
      (node (ref "R20") (pin "2") (pinfunction "2_2") (pintype "passive"))
    )
    (net (code "38") (name "Net-(IC2D-OUT)") (class "Default")
      (node (ref "C12") (pin "2") (pinfunction "2_2") (pintype "passive"))
      (node (ref "IC2") (pin "14") (pinfunction "OUT_14") (pintype "output"))
      (node (ref "OUT4") (pin "P$1_TIP") (pinfunction "TIP_P$1_TIP") (pintype "passive"))
      (node (ref "R19") (pin "2") (pinfunction "2_2") (pintype "passive"))
      (node (ref "R23") (pin "2") (pinfunction "2_2") (pintype "passive"))
    )
    (net (code "39") (name "Net-(IC4-CAP+)") (class "Default")
      (node (ref "C15") (pin "+") (pinfunction "+_+") (pintype "passive"))
      (node (ref "IC4") (pin "2") (pinfunction "CAP+_2") (pintype "passive"))
    )
    (net (code "40") (name "Net-(IC4-CAP-)") (class "Default")
      (node (ref "C15") (pin "-") (pinfunction "-_-") (pintype "passive"))
      (node (ref "IC4") (pin "4") (pinfunction "CAP-_4") (pintype "passive"))
    )
    (net (code "41") (name "Net-(IC4-VOUT)") (class "Default")
      (node (ref "IC4") (pin "5") (pinfunction "VOUT_5") (pintype "output"))
      (node (ref "SW1") (pin "NC2") (pinfunction "NC2_NC2") (pintype "bidirectional"))
    )
    (net (code "42") (name "Net-(LED1-PadA)") (class "Default")
      (node (ref "LED1") (pin "A") (pinfunction "A_A") (pintype "passive"))
      (node (ref "R2") (pin "1") (pinfunction "1_1") (pintype "passive"))
    )
    (net (code "43") (name "Net-(LED2-PadA)") (class "Default")
      (node (ref "LED2") (pin "A") (pinfunction "A_A") (pintype "passive"))
      (node (ref "R8") (pin "1") (pinfunction "1_1") (pintype "passive"))
    )
    (net (code "44") (name "Net-(LED3-PadA)") (class "Default")
      (node (ref "LED3") (pin "A") (pinfunction "A_A") (pintype "passive"))
      (node (ref "R16") (pin "1") (pinfunction "1_1") (pintype "passive"))
    )
    (net (code "45") (name "Net-(LED4-PadA)") (class "Default")
      (node (ref "LED4") (pin "A") (pinfunction "A_A") (pintype "passive"))
      (node (ref "R23") (pin "1") (pinfunction "1_1") (pintype "passive"))
    )
    (net (code "46") (name "Net-(LED5-PadA)") (class "Default")
      (node (ref "LED5") (pin "A") (pinfunction "A_A") (pintype "passive"))
      (node (ref "R27") (pin "1") (pinfunction "1_1") (pintype "passive"))
    )
    (net (code "47") (name "Net-(NEUZ_OUT-TIP)") (class "Default")
      (node (ref "C22") (pin "1") (pinfunction "1_1") (pintype "passive"))
      (node (ref "NEUZ_OUT") (pin "P$1_TIP") (pinfunction "TIP_P$1_TIP") (pintype "passive"))
      (node (ref "R26") (pin "2") (pinfunction "2_2") (pintype "passive"))
    )
    (net (code "48") (name "Net-(PAN_CV_IN-TIP)") (class "Default")
      (node (ref "PAN_CV_IN") (pin "P$1_TIP") (pinfunction "TIP_P$1_TIP") (pintype "passive"))
      (node (ref "R1") (pin "2") (pinfunction "2_2") (pintype "passive"))
    )
    (net (code "49") (name "Net-(SW1-C)") (class "Default")
      (node (ref "G1") (pin "+") (pinfunction "+_+") (pintype "passive"))
      (node (ref "SW1") (pin "C1") (pinfunction "C_C1") (pintype "bidirectional"))
    )
    (net (code "50") (name "Net-(SW1-NC)") (class "Default")
      (node (ref "D11") (pin "A") (pinfunction "A_A") (pintype "passive"))
      (node (ref "SW1") (pin "NC1") (pinfunction "NC_NC1") (pintype "bidirectional"))
    )
    (net (code "51") (name "Net-(VOCT_1-TIP)") (class "Default")
      (node (ref "R49") (pin "2") (pinfunction "2_2") (pintype "passive"))
      (node (ref "VOCT_1") (pin "P$1_TIP") (pinfunction "TIP_P$1_TIP") (pintype "passive"))
    )
    (net (code "52") (name "Net-(VOCT_2-TIP)") (class "Default")
      (node (ref "R50") (pin "2") (pinfunction "2_2") (pintype "passive"))
      (node (ref "VOCT_2") (pin "P$1_TIP") (pinfunction "TIP_P$1_TIP") (pintype "passive"))
    )
    (net (code "53") (name "PAN_CV") (class "Default")
      (node (ref "IC1") (pin "24") (pinfunction "AN8/OC1/RB8_24") (pintype "bidirectional"))
      (node (ref "R1") (pin "1") (pinfunction "1_1") (pintype "passive"))
    )
    (net (code "54") (name "PGC") (class "Default")
      (node (ref "IC1") (pin "18") (pinfunction "PGC/EMUC/U1RX/SDI1/SDA/RF2_18") (pintype "bidirectional"))
      (node (ref "PROGRAMMER") (pin "5") (pinfunction "5_5") (pintype "passive"))
    )
    (net (code "55") (name "SCK") (class "Default")
      (node (ref "IC1") (pin "16") (pinfunction "SCK1/INT0/RF6_16") (pintype "bidirectional"))
      (node (ref "IC5") (pin "3") (pinfunction "SCK_3") (pintype "input"))
      (node (ref "IC6") (pin "3") (pinfunction "SCK_3") (pintype "input"))
    )
    (net (code "56") (name "SS") (class "Default")
      (node (ref "IC1") (pin "15") (pinfunction "EMUC2/IC1/INT1/RD8_15") (pintype "bidirectional"))
      (node (ref "IC6") (pin "2") (pinfunction "~{CS}_2") (pintype "input"))
    )
    (net (code "57") (name "SS_2") (class "Default")
      (node (ref "IC1") (pin "22") (pinfunction "CN17/RF4_22") (pintype "bidirectional"))
      (node (ref "IC5") (pin "2") (pinfunction "~{CS}_2") (pintype "input"))
    )
    (net (code "58") (name "V_OCT_1") (class "Default")
      (node (ref "IC1") (pin "26") (pinfunction "AN6/OCFA/RB6_26") (pintype "bidirectional"))
      (node (ref "R49") (pin "1") (pinfunction "1_1") (pintype "passive"))
    )
    (net (code "59") (name "V_OCT_2") (class "Default")
      (node (ref "IC1") (pin "25") (pinfunction "EMUD2/AN7/RB7_25") (pintype "bidirectional"))
      (node (ref "R50") (pin "1") (pinfunction "1_1") (pintype "passive"))
    )
    (net (code "60") (name "unconnected-(IC1-EMUC1{slash}SOSCO{slash}T1CK{slash}U1ARX{slash}CN0{slash}RC14-Pad12)") (class "Default")
      (node (ref "IC1") (pin "12") (pinfunction "EMUC1/SOSCO/T1CK/U1ARX/CN0/RC14_12") (pintype "bidirectional"))
    )
    (net (code "61") (name "unconnected-(IC1-EMUD1{slash}SOSCI{slash}T2CK{slash}U1ATX{slash}CN1{slash}RC13-Pad11)") (class "Default")
      (node (ref "IC1") (pin "11") (pinfunction "EMUD1/SOSCI/T2CK/U1ATX/CN1/RC13_11") (pintype "bidirectional"))
    )
    (net (code "62") (name "unconnected-(IC1-OSC1{slash}CLKI-Pad9)") (class "Default")
      (node (ref "IC1") (pin "9") (pinfunction "OSC1/CLKI_9") (pintype "input"))
    )
    (net (code "63") (name "unconnected-(IC1-OSC2{slash}CLKO{slash}RC15-Pad10)") (class "Default")
      (node (ref "IC1") (pin "10") (pinfunction "OSC2/CLKO/RC15_10") (pintype "bidirectional"))
    )
    (net (code "64") (name "unconnected-(IC4-LV-Pad6)") (class "Default")
      (node (ref "IC4") (pin "6") (pinfunction "LV_6") (pintype "passive"))
    )
    (net (code "65") (name "unconnected-(IC4-NC-Pad1)") (class "Default")
      (node (ref "IC4") (pin "1") (pinfunction "NC_1") (pintype "no_connect"))
    )
    (net (code "66") (name "unconnected-(IC4-OSC-Pad7)") (class "Default")
      (node (ref "IC4") (pin "7") (pinfunction "OSC_7") (pintype "output"))
    )
    (net (code "67") (name "unconnected-(NEUZ_OUT-SWITCH-PadP$2_SWITCH)") (class "Default")
      (node (ref "NEUZ_OUT") (pin "P$2_SWITCH") (pinfunction "SWITCH_P$2_SWITCH") (pintype "passive"))
    )
    (net (code "68") (name "unconnected-(OUT1-SWITCH-PadP$2_SWITCH)") (class "Default")
      (node (ref "OUT1") (pin "P$2_SWITCH") (pinfunction "SWITCH_P$2_SWITCH") (pintype "passive"))
    )
    (net (code "69") (name "unconnected-(OUT2-SWITCH-PadP$2_SWITCH)") (class "Default")
      (node (ref "OUT2") (pin "P$2_SWITCH") (pinfunction "SWITCH_P$2_SWITCH") (pintype "passive"))
    )
    (net (code "70") (name "unconnected-(OUT3-SWITCH-PadP$2_SWITCH)") (class "Default")
      (node (ref "OUT3") (pin "P$2_SWITCH") (pinfunction "SWITCH_P$2_SWITCH") (pintype "passive"))
    )
    (net (code "71") (name "unconnected-(OUT4-SWITCH-PadP$2_SWITCH)") (class "Default")
      (node (ref "OUT4") (pin "P$2_SWITCH") (pinfunction "SWITCH_P$2_SWITCH") (pintype "passive"))
    )
    (net (code "72") (name "unconnected-(PROGRAMMER-Pad6)") (class "Default")
      (node (ref "PROGRAMMER") (pin "6") (pinfunction "6_6") (pintype "passive"))
    )
    (net (code "73") (name "unconnected-(SW1-NO-PadNO1)") (class "Default")
      (node (ref "SW1") (pin "NO1") (pinfunction "NO_NO1") (pintype "bidirectional"))
    )
    (net (code "74") (name "unconnected-(SW1-PadNO2)") (class "Default")
      (node (ref "SW1") (pin "NO2") (pinfunction "NO2_NO2") (pintype "bidirectional"))
    )
  )
)
